# Power.net
KiCad netlist of a schematic drawn in Altium Designer
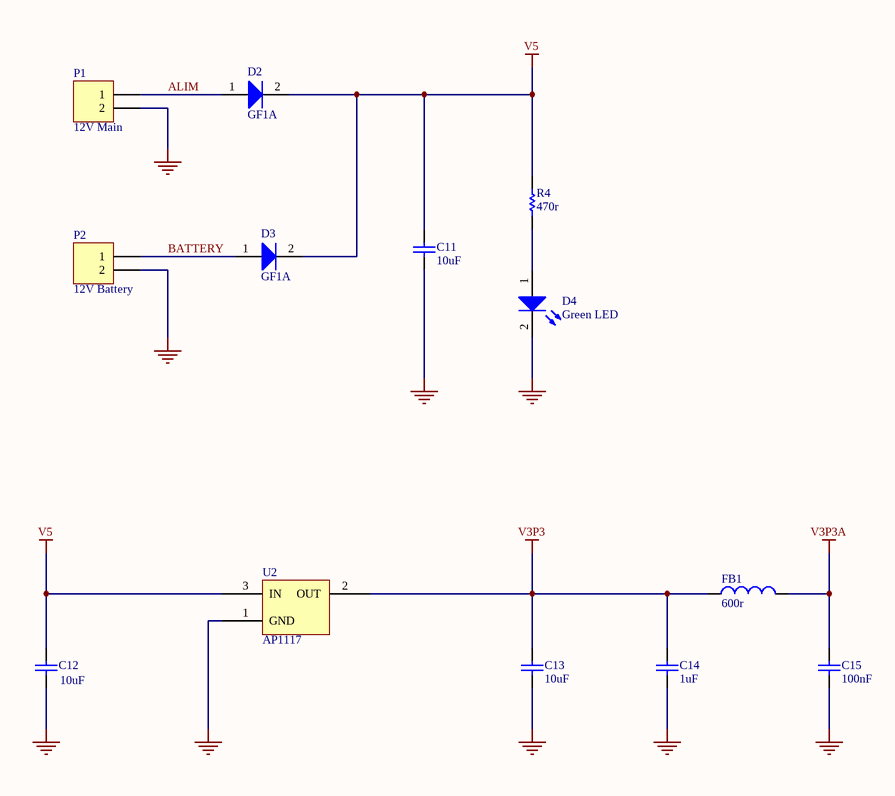
[diagram p0: Power.SchDoc]

(export (version "E")
  (design (tool "Eeschema 10.0.6"))
  (components
    (comp (ref "C11")
      (value "10uF")
      (footprint "CAPC2012N")
      (description "Capacitor")
      (fields (field (name "PUBLISHER") "Altium Limited"))
      (libsource (lib "Miscellaneous Devices") (part "Cap"))
    )
    (comp (ref "C12")
      (value "10uF")
      (footprint "CAPC2012N")
      (description "Capacitor")
      (fields (field (name "PUBLISHER") "Altium Limited"))
      (libsource (lib "Miscellaneous Devices") (part "Cap"))
    )
    (comp (ref "C13")
      (value "10uF")
      (footprint "CAPC2012N")
      (description "Capacitor")
      (fields (field (name "PUBLISHER") "Altium Limited"))
      (libsource (lib "Miscellaneous Devices") (part "Cap"))
    )
    (comp (ref "C14")
      (value "1uF")
      (footprint "CAPC1608N")
      (description "Capacitor")
      (fields (field (name "PUBLISHER") "Altium Limited"))
      (libsource (lib "Miscellaneous Devices") (part "Cap"))
    )
    (comp (ref "C15")
      (value "100nF")
      (footprint "CAPC1608N")
      (description "Capacitor")
      (fields (field (name "PUBLISHER") "Altium Limited"))
      (libsource (lib "Miscellaneous Devices") (part "Cap"))
    )
    (comp (ref "D2")
      (value "GF1A")
      (footprint "SMA/DO-214AC_21")
      (description "Default Diode")
      (fields (field (name "PUBLISHER") "Altium Limited"))
      (libsource (lib "Miscellaneous Devices") (part "Diode"))
    )
    (comp (ref "D3")
      (value "GF1A")
      (footprint "SMA/DO-214AC_21")
      (description "Default Diode")
      (fields (field (name "PUBLISHER") "Altium Limited"))
      (libsource (lib "Miscellaneous Devices") (part "Diode"))
    )
    (comp (ref "D4")
      (value "Green LED")
      (footprint "LED 0805")
      (description "Typical RED, GREEN, YELLOW, AMBER GaAs LED")
      (fields (field (name "PUBLISHER") "Altium Limited"))
      (libsource (lib "Miscellaneous Devices") (part "LED2"))
    )
    (comp (ref "FB1")
      (value "600r")
      (footprint "INDC1608AN")
      (description "Inductor")
      (fields (field (name "PUBLISHER") "Altium Limited"))
      (libsource (lib "Miscellaneous Devices") (part "Inductor"))
    )
    (comp (ref "P1")
      (value "12V Main")
      (footprint "PHOENIX_1985195")
      (description "Header, 2-Pin")
      (fields (field (name "PUBLISHER") "Altium Limited"))
      (libsource (lib "Miscellaneous Connectors") (part "Header 2"))
    )
    (comp (ref "P2")
      (value "12V Battery")
      (footprint "PHOENIX_1985195")
      (description "Header, 2-Pin")
      (fields (field (name "PUBLISHER") "Altium Limited"))
      (libsource (lib "Miscellaneous Connectors") (part "Header 2"))
    )
    (comp (ref "R4")
      (value "470r")
      (footprint "RESC1608N")
      (description "Resistor")
      (fields (field (name "PUBLISHER") "Altium Limited"))
      (libsource (lib "Miscellaneous Devices") (part "Res1"))
    )
    (comp (ref "U2")
      (value "AP1117")
      (footprint "TD03B_N")
      (description "1A LDO, 18V input, DPAK")
      (libsource (lib "PIC") (part "AP1117"))
    )
  )
  (nets
    (net (code "1") (name "/ALIM") (class "Default")
      (node (ref "D2") (pin "1") (pinfunction "A_1") (pintype "passive"))
      (node (ref "P1") (pin "1") (pinfunction "1_1") (pintype "passive"))
    )
    (net (code "2") (name "/BATTERY") (class "Default")
      (node (ref "D3") (pin "1") (pinfunction "A_1") (pintype "passive"))
      (node (ref "P2") (pin "1") (pinfunction "1_1") (pintype "passive"))
    )
    (net (code "3") (name "GND") (class "Default")
      (node (ref "C11") (pin "1") (pinfunction "1_1") (pintype "passive"))
      (node (ref "C12") (pin "1") (pinfunction "1_1") (pintype "passive"))
      (node (ref "C13") (pin "1") (pinfunction "1_1") (pintype "passive"))
      (node (ref "C14") (pin "1") (pinfunction "1_1") (pintype "passive"))
      (node (ref "C15") (pin "1") (pinfunction "1_1") (pintype "passive"))
      (node (ref "D4") (pin "2") (pinfunction "K_2") (pintype "passive"))
      (node (ref "P1") (pin "2") (pinfunction "2_2") (pintype "passive"))
      (node (ref "P2") (pin "2") (pinfunction "2_2") (pintype "passive"))
      (node (ref "U2") (pin "1") (pinfunction "GND_1") (pintype "passive"))
    )
    (net (code "4") (name "Net-(D4-A)") (class "Default")
      (node (ref "D4") (pin "1") (pinfunction "A_1") (pintype "passive"))
      (node (ref "R4") (pin "1") (pinfunction "1_1") (pintype "passive"))
    )
    (net (code "5") (name "V3P3") (class "Default")
      (node (ref "C13") (pin "2") (pinfunction "2_2") (pintype "passive"))
      (node (ref "C14") (pin "2") (pinfunction "2_2") (pintype "passive"))
      (node (ref "FB1") (pin "1") (pinfunction "1_1") (pintype "passive"))
      (node (ref "U2") (pin "2") (pinfunction "OUT_2") (pintype "passive"))
    )
    (net (code "6") (name "V3P3A") (class "Default")
      (node (ref "C15") (pin "2") (pinfunction "2_2") (pintype "passive"))
      (node (ref "FB1") (pin "2") (pinfunction "2_2") (pintype "passive"))
    )
    (net (code "7") (name "V5") (class "Default")
      (node (ref "C11") (pin "2") (pinfunction "2_2") (pintype "passive"))
      (node (ref "C12") (pin "2") (pinfunction "2_2") (pintype "passive"))
      (node (ref "D2") (pin "2") (pinfunction "K_2") (pintype "passive"))
      (node (ref "D3") (pin "2") (pinfunction "K_2") (pintype "passive"))
      (node (ref "R4") (pin "2") (pinfunction "2_2") (pintype "passive"))
      (node (ref "U2") (pin "3") (pinfunction "IN_3") (pintype "passive"))
    )
  )
)
